# IIC_LCD.net
KiCad netlist of a schematic drawn in Altium Designer
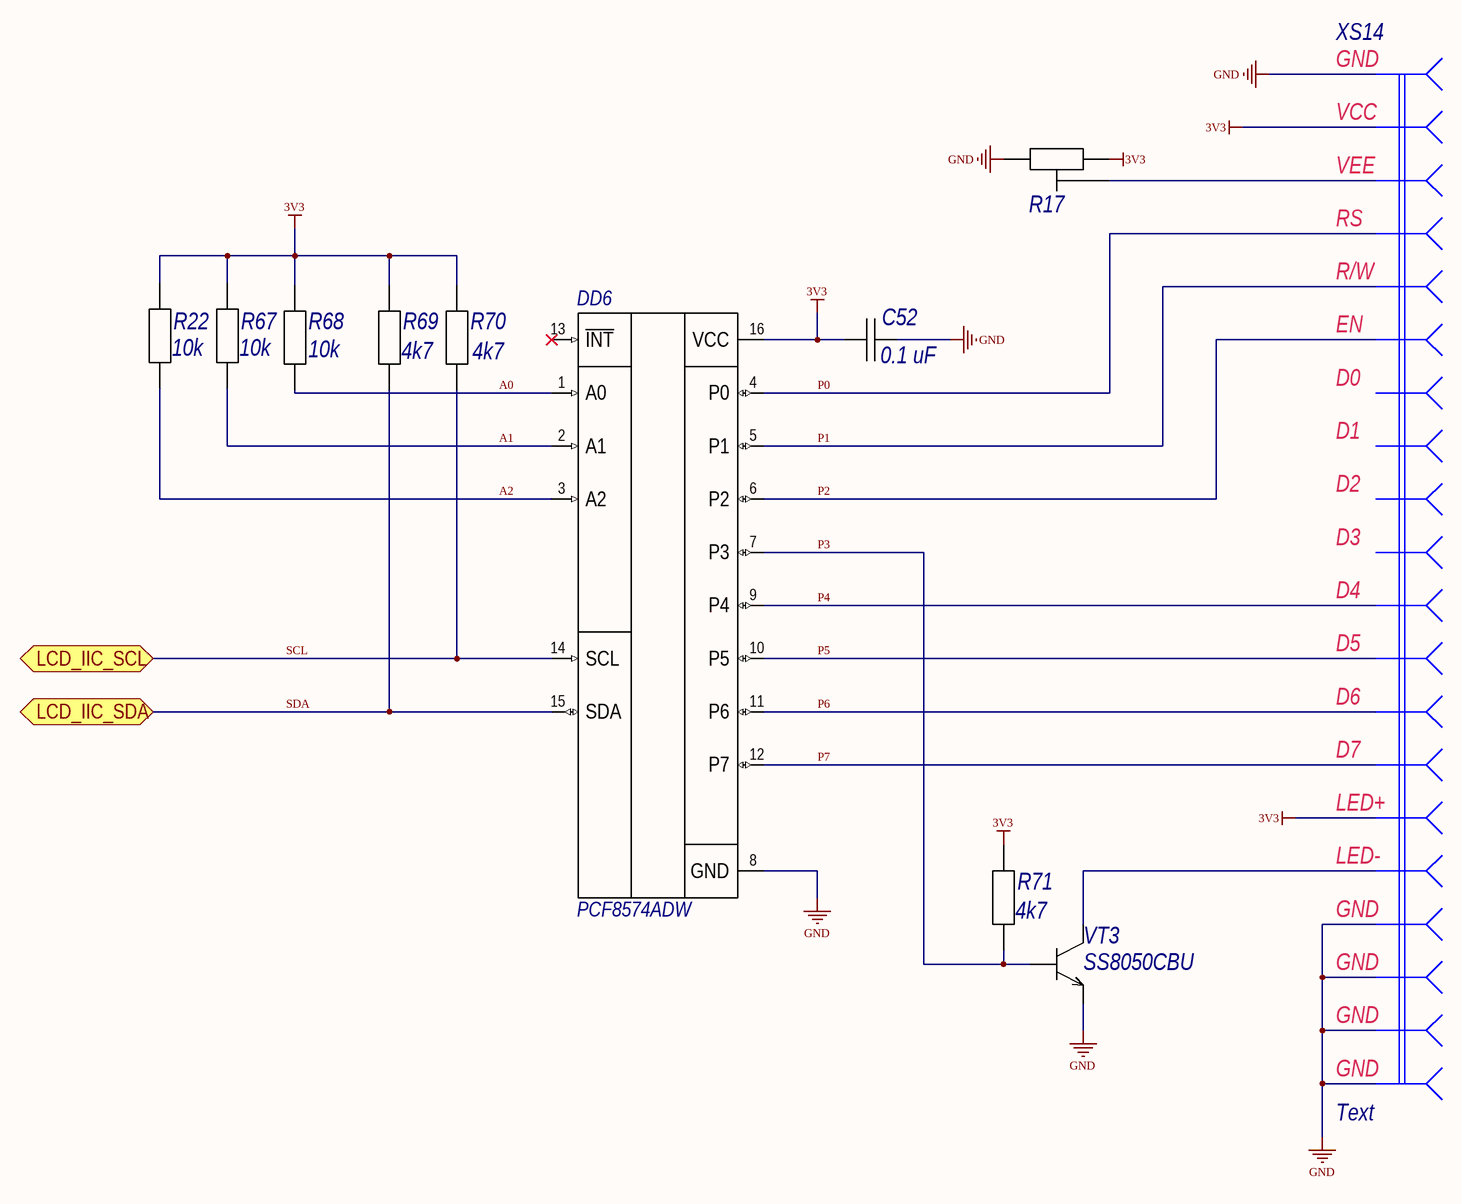
[diagram p0: IIC_LCD.SchDoc]

(export (version "E")
  (design (tool "Eeschema 10.0.6"))
  (components
    (comp (ref "C52")
      (value "0.1 uF")
      (footprint "C0805C")
      (fields (field (name "PUBLISHER") "Andrew Danich"))
      (libsource (lib "PA_control_board") (part "CAP_0805"))
    )
    (comp (ref "DD6")
      (value "PCF8574ADW")
      (footprint "SOIC127P1030X265-16N")
      (description "Remote 8-Bit I/O Expander for I2C-Bus 16-SOIC -40 to 85")
      (fields (field (name "MF") "Texas Instruments"))
      (libsource (lib "PA_control_board") (part "PCF8574ADW"))
    )
    (comp (ref "R17")
      (value "RES_VAR")
      (footprint "TRIM_3296W-1-254LF")
      (fields (field (name "PUBLISHER") "Andrew Danich"))
      (libsource (lib "PA_control_board") (part "RES_VAR"))
    )
    (comp (ref "R22")
      (value "10k")
      (footprint "C0805R")
      (fields (field (name "PUBLISHER") "Andrew Danich"))
      (libsource (lib "PA_control_board") (part "RES_0805"))
    )
    (comp (ref "R67")
      (value "10k")
      (footprint "C0805R")
      (fields (field (name "PUBLISHER") "Andrew Danich"))
      (libsource (lib "PA_control_board") (part "RES_0805"))
    )
    (comp (ref "R68")
      (value "10k")
      (footprint "C0805R")
      (fields (field (name "PUBLISHER") "Andrew Danich"))
      (libsource (lib "PA_control_board") (part "RES_0805"))
    )
    (comp (ref "R69")
      (value "4k7")
      (footprint "C0805R")
      (fields (field (name "PUBLISHER") "Andrew Danich"))
      (libsource (lib "PA_control_board") (part "RES_0805"))
    )
    (comp (ref "R70")
      (value "4k7")
      (footprint "C0805R")
      (fields (field (name "PUBLISHER") "Andrew Danich"))
      (libsource (lib "PA_control_board") (part "RES_0805"))
    )
    (comp (ref "R71")
      (value "4k7")
      (footprint "C0805R")
      (fields (field (name "PUBLISHER") "Andrew Danich"))
      (libsource (lib "PA_control_board") (part "RES_0805"))
    )
    (comp (ref "VT3")
      (value "SS8050CBU")
      (footprint "TO-92-A")
      (fields (field (name "PUBLISHER") "Andrew Danich"))
      (libsource (lib "PA_control_board") (part "SS8050CBU"))
    )
    (comp (ref "XS14")
      (value "Text")
      (footprint "IDC-20")
      (fields (field (name "PUBLISHER") "Andrew Danich"))
      (libsource (lib "PA_control_board") (part "CONNECT_LCD"))
    )
  )
  (nets
    (net (code "1") (name "/A0") (class "Default")
      (node (ref "DD6") (pin "1") (pinfunction "A0_1") (pintype "input"))
      (node (ref "R68") (pin "1") (pinfunction "1_1") (pintype "passive"))
    )
    (net (code "2") (name "/A1") (class "Default")
      (node (ref "DD6") (pin "2") (pinfunction "A1_2") (pintype "input"))
      (node (ref "R67") (pin "1") (pinfunction "1_1") (pintype "passive"))
    )
    (net (code "3") (name "/A2") (class "Default")
      (node (ref "DD6") (pin "3") (pinfunction "A2_3") (pintype "input"))
      (node (ref "R22") (pin "1") (pinfunction "1_1") (pintype "passive"))
    )
    (net (code "4") (name "/P0") (class "Default")
      (node (ref "DD6") (pin "4") (pinfunction "P0_4") (pintype "bidirectional"))
      (node (ref "XS14") (pin "4") (pintype "passive"))
    )
    (net (code "5") (name "/P1") (class "Default")
      (node (ref "DD6") (pin "5") (pinfunction "P1_5") (pintype "bidirectional"))
      (node (ref "XS14") (pin "5") (pintype "passive"))
    )
    (net (code "6") (name "/P2") (class "Default")
      (node (ref "DD6") (pin "6") (pinfunction "P2_6") (pintype "bidirectional"))
      (node (ref "XS14") (pin "6") (pintype "passive"))
    )
    (net (code "7") (name "/P3") (class "Default")
      (node (ref "DD6") (pin "7") (pinfunction "P3_7") (pintype "bidirectional"))
      (node (ref "R71") (pin "1") (pinfunction "1_1") (pintype "passive"))
      (node (ref "VT3") (pin "1") (pinfunction "Б_1") (pintype "passive"))
    )
    (net (code "8") (name "/P4") (class "Default")
      (node (ref "DD6") (pin "9") (pinfunction "P4_9") (pintype "bidirectional"))
      (node (ref "XS14") (pin "11") (pintype "passive"))
    )
    (net (code "9") (name "/P5") (class "Default")
      (node (ref "DD6") (pin "10") (pinfunction "P5_10") (pintype "bidirectional"))
      (node (ref "XS14") (pin "12") (pintype "passive"))
    )
    (net (code "10") (name "/P6") (class "Default")
      (node (ref "DD6") (pin "11") (pinfunction "P6_11") (pintype "bidirectional"))
      (node (ref "XS14") (pin "13") (pintype "passive"))
    )
    (net (code "11") (name "/P7") (class "Default")
      (node (ref "DD6") (pin "12") (pinfunction "P7_12") (pintype "bidirectional"))
      (node (ref "XS14") (pin "14") (pintype "passive"))
    )
    (net (code "12") (name "/SCL") (class "Default")
      (node (ref "DD6") (pin "14") (pinfunction "SCL_14") (pintype "input"))
      (node (ref "R70") (pin "1") (pinfunction "1_1") (pintype "passive"))
    )
    (net (code "13") (name "/SDA") (class "Default")
      (node (ref "DD6") (pin "15") (pinfunction "SDA_15") (pintype "bidirectional"))
      (node (ref "R69") (pin "1") (pinfunction "1_1") (pintype "passive"))
    )
    (net (code "14") (name "3V3") (class "Default")
      (node (ref "C52") (pin "2") (pinfunction "2_2") (pintype "passive"))
      (node (ref "DD6") (pin "16") (pinfunction "VCC_16") (pintype "power_in"))
      (node (ref "R17") (pin "1") (pinfunction "1_1") (pintype "passive"))
      (node (ref "R22") (pin "2") (pinfunction "2_2") (pintype "passive"))
      (node (ref "R67") (pin "2") (pinfunction "2_2") (pintype "passive"))
      (node (ref "R68") (pin "2") (pinfunction "2_2") (pintype "passive"))
      (node (ref "R69") (pin "2") (pinfunction "2_2") (pintype "passive"))
      (node (ref "R70") (pin "2") (pinfunction "2_2") (pintype "passive"))
      (node (ref "R71") (pin "2") (pinfunction "2_2") (pintype "passive"))
      (node (ref "XS14") (pin "15") (pintype "passive"))
      (node (ref "XS14") (pin "2") (pintype "passive"))
    )
    (net (code "15") (name "GND") (class "Default")
      (node (ref "C52") (pin "1") (pinfunction "1_1") (pintype "passive"))
      (node (ref "DD6") (pin "8") (pinfunction "GND_8") (pintype "power_in"))
      (node (ref "R17") (pin "3") (pinfunction "3_3") (pintype "passive"))
      (node (ref "VT3") (pin "3") (pinfunction "Э_3") (pintype "passive"))
      (node (ref "XS14") (pin "1") (pintype "passive"))
      (node (ref "XS14") (pin "17") (pintype "passive"))
      (node (ref "XS14") (pin "18") (pintype "passive"))
      (node (ref "XS14") (pin "19") (pintype "passive"))
      (node (ref "XS14") (pin "20") (pintype "passive"))
    )
    (net (code "16") (name "Net-(R17-Pad2)") (class "Default")
      (node (ref "R17") (pin "2") (pinfunction "2_2") (pintype "passive"))
      (node (ref "XS14") (pin "3") (pintype "passive"))
    )
    (net (code "17") (name "Net-(VT3-К)") (class "Default")
      (node (ref "VT3") (pin "2") (pinfunction "К_2") (pintype "passive"))
      (node (ref "XS14") (pin "16") (pintype "passive"))
    )
    (net (code "18") (name "unconnected-(DD6-~{INT}-Pad13)") (class "Default")
      (node (ref "DD6") (pin "13") (pinfunction "~{INT}_13") (pintype "input+no_connect"))
    )
    (net (code "19") (name "unconnected-(XS14-Pad7)") (class "Default")
      (node (ref "XS14") (pin "7") (pintype "passive"))
    )
    (net (code "20") (name "unconnected-(XS14-Pad8)") (class "Default")
      (node (ref "XS14") (pin "8") (pintype "passive"))
    )
    (net (code "21") (name "unconnected-(XS14-Pad9)") (class "Default")
      (node (ref "XS14") (pin "9") (pintype "passive"))
    )
    (net (code "22") (name "unconnected-(XS14-Pad10)") (class "Default")
      (node (ref "XS14") (pin "10") (pintype "passive"))
    )
  )
)
